# AWG_SFPs.net
KiCad netlist of a schematic drawn in Altium Designer
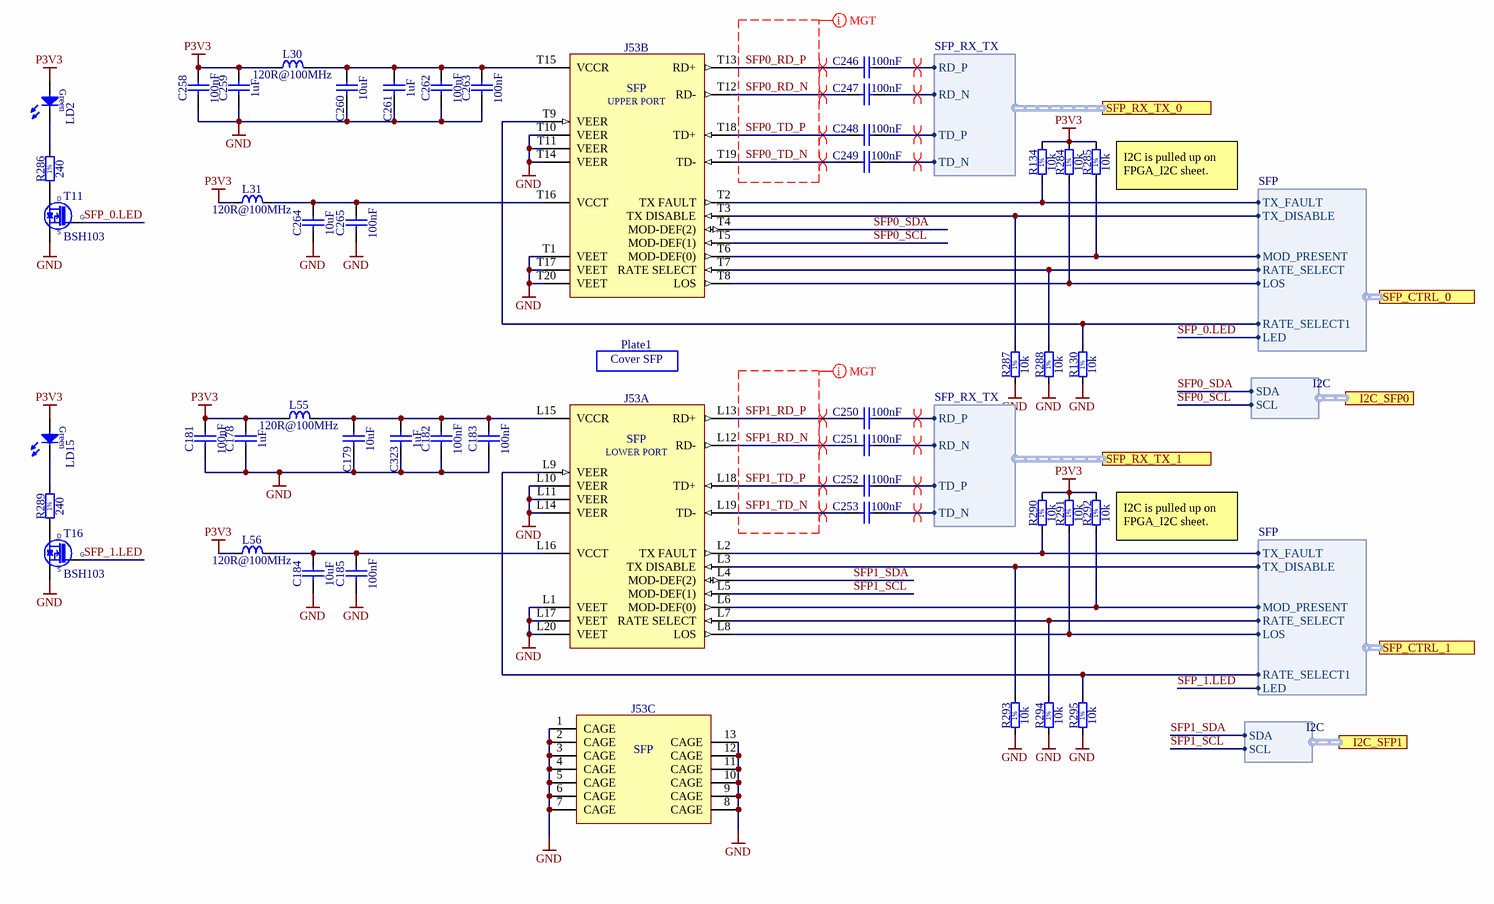
[diagram p0: AWG_SFPs.SchDoc]

(export (version "E")
  (design (tool "Eeschema 10.0.6"))
  (components
    (comp (ref "C178")
      (value "1uF")
      (footprint "CAPC1005X55N")
      (description "Non-polarised capacitor")
      (fields
        (field (name "PART NUMBER") "CC0402_1UF_16V_10%_X5R")
        (field (name "VOLTAGE") "16V")
        (field (name "AUTHOR") "CERN DEM JLC")
      )
      (libsource (lib "Capacitors") (part "Capacitor - non polarized"))
    )
    (comp (ref "C179")
      (value "10uF")
      (footprint "CAPC2012X95N")
      (description "Non-polarised capacitor")
      (fields
        (field (name "PART NUMBER") "CC0805_10UF_25V_10%_X5R")
        (field (name "VOLTAGE") "25V")
        (field (name "AUTHOR") "CERN DEM JLC")
      )
      (libsource (lib "Capacitors") (part "Capacitor - non polarized"))
    )
    (comp (ref "C181")
      (value "100nF")
      (footprint "CAPC1005X55N")
      (description "Non-polarised capacitor")
      (fields
        (field (name "PART NUMBER") "CC0402_100NF_16V_10%_X7R")
        (field (name "VOLTAGE") "16V")
        (field (name "AUTHOR") "CERN DEM JLC")
      )
      (libsource (lib "Capacitors") (part "Capacitor - non polarized"))
    )
    (comp (ref "C182")
      (value "100nF")
      (footprint "CAPC1005X55N")
      (description "Non-polarised capacitor")
      (fields
        (field (name "PART NUMBER") "CC0402_100NF_16V_10%_X7R")
        (field (name "VOLTAGE") "16V")
        (field (name "AUTHOR") "CERN DEM JLC")
      )
      (libsource (lib "Capacitors") (part "Capacitor - non polarized"))
    )
    (comp (ref "C183")
      (value "100nF")
      (footprint "CAPC1005X55N")
      (description "Non-polarised capacitor")
      (fields
        (field (name "PART NUMBER") "CC0402_100NF_16V_10%_X7R")
        (field (name "VOLTAGE") "16V")
        (field (name "AUTHOR") "CERN DEM JLC")
      )
      (libsource (lib "Capacitors") (part "Capacitor - non polarized"))
    )
    (comp (ref "C184")
      (value "10uF")
      (footprint "CAPC2012X95N")
      (description "Non-polarised capacitor")
      (fields
        (field (name "PART NUMBER") "CC0805_10UF_25V_10%_X5R")
        (field (name "VOLTAGE") "25V")
        (field (name "AUTHOR") "CERN DEM JLC")
      )
      (libsource (lib "Capacitors") (part "Capacitor - non polarized"))
    )
    (comp (ref "C185")
      (value "100nF")
      (footprint "CAPC1005X55N")
      (description "Non-polarised capacitor")
      (fields
        (field (name "PART NUMBER") "CC0402_100NF_16V_10%_X7R")
        (field (name "VOLTAGE") "16V")
        (field (name "AUTHOR") "CERN DEM JLC")
      )
      (libsource (lib "Capacitors") (part "Capacitor - non polarized"))
    )
    (comp (ref "C246")
      (value "100nF")
      (footprint "CAPC0603X33N")
      (description "Non-polarised capacitor")
      (fields
        (field (name "PART NUMBER") "CC0201_100NF_6.3V_10%_X5R")
        (field (name "VOLTAGE") "6.3V")
        (field (name "AUTHOR") "CERN DEM JLC")
      )
      (libsource (lib "Capacitors") (part "Capacitor - non polarized"))
    )
    (comp (ref "C247")
      (value "100nF")
      (footprint "CAPC0603X33N")
      (description "Non-polarised capacitor")
      (fields
        (field (name "PART NUMBER") "CC0201_100NF_6.3V_10%_X5R")
        (field (name "VOLTAGE") "6.3V")
        (field (name "AUTHOR") "CERN DEM JLC")
      )
      (libsource (lib "Capacitors") (part "Capacitor - non polarized"))
    )
    (comp (ref "C248")
      (value "100nF")
      (footprint "CAPC0603X33N")
      (description "Non-polarised capacitor")
      (fields
        (field (name "PART NUMBER") "CC0201_100NF_6.3V_10%_X5R")
        (field (name "VOLTAGE") "6.3V")
        (field (name "AUTHOR") "CERN DEM JLC")
      )
      (libsource (lib "Capacitors") (part "Capacitor - non polarized"))
    )
    (comp (ref "C249")
      (value "100nF")
      (footprint "CAPC0603X33N")
      (description "Non-polarised capacitor")
      (fields
        (field (name "PART NUMBER") "CC0201_100NF_6.3V_10%_X5R")
        (field (name "VOLTAGE") "6.3V")
        (field (name "AUTHOR") "CERN DEM JLC")
      )
      (libsource (lib "Capacitors") (part "Capacitor - non polarized"))
    )
    (comp (ref "C250")
      (value "100nF")
      (footprint "CAPC0603X33N")
      (description "Non-polarised capacitor")
      (fields
        (field (name "PART NUMBER") "CC0201_100NF_6.3V_10%_X5R")
        (field (name "VOLTAGE") "6.3V")
        (field (name "AUTHOR") "CERN DEM JLC")
      )
      (libsource (lib "Capacitors") (part "Capacitor - non polarized"))
    )
    (comp (ref "C251")
      (value "100nF")
      (footprint "CAPC0603X33N")
      (description "Non-polarised capacitor")
      (fields
        (field (name "PART NUMBER") "CC0201_100NF_6.3V_10%_X5R")
        (field (name "VOLTAGE") "6.3V")
        (field (name "AUTHOR") "CERN DEM JLC")
      )
      (libsource (lib "Capacitors") (part "Capacitor - non polarized"))
    )
    (comp (ref "C252")
      (value "100nF")
      (footprint "CAPC0603X33N")
      (description "Non-polarised capacitor")
      (fields
        (field (name "PART NUMBER") "CC0201_100NF_6.3V_10%_X5R")
        (field (name "VOLTAGE") "6.3V")
        (field (name "AUTHOR") "CERN DEM JLC")
      )
      (libsource (lib "Capacitors") (part "Capacitor - non polarized"))
    )
    (comp (ref "C253")
      (value "100nF")
      (footprint "CAPC0603X33N")
      (description "Non-polarised capacitor")
      (fields
        (field (name "PART NUMBER") "CC0201_100NF_6.3V_10%_X5R")
        (field (name "VOLTAGE") "6.3V")
        (field (name "AUTHOR") "CERN DEM JLC")
      )
      (libsource (lib "Capacitors") (part "Capacitor - non polarized"))
    )
    (comp (ref "C258")
      (value "100nF")
      (footprint "CAPC1005X55N")
      (description "Non-polarised capacitor")
      (fields
        (field (name "PART NUMBER") "CC0402_100NF_16V_10%_X7R")
        (field (name "VOLTAGE") "16V")
        (field (name "AUTHOR") "CERN DEM JLC")
      )
      (libsource (lib "Capacitors") (part "Capacitor - non polarized"))
    )
    (comp (ref "C259")
      (value "1uF")
      (footprint "CAPC1005X55N")
      (description "Non-polarised capacitor")
      (fields
        (field (name "PART NUMBER") "CC0402_1UF_16V_10%_X5R")
        (field (name "VOLTAGE") "16V")
        (field (name "AUTHOR") "CERN DEM JLC")
      )
      (libsource (lib "Capacitors") (part "Capacitor - non polarized"))
    )
    (comp (ref "C260")
      (value "10uF")
      (footprint "CAPC2012X95N")
      (description "Non-polarised capacitor")
      (fields
        (field (name "PART NUMBER") "CC0805_10UF_25V_10%_X5R")
        (field (name "VOLTAGE") "25V")
        (field (name "AUTHOR") "CERN DEM JLC")
      )
      (libsource (lib "Capacitors") (part "Capacitor - non polarized"))
    )
    (comp (ref "C261")
      (value "1uF")
      (footprint "CAPC1005X55N")
      (description "Non-polarised capacitor")
      (fields
        (field (name "PART NUMBER") "CC0402_1UF_16V_10%_X5R")
        (field (name "VOLTAGE") "16V")
        (field (name "AUTHOR") "CERN DEM JLC")
      )
      (libsource (lib "Capacitors") (part "Capacitor - non polarized"))
    )
    (comp (ref "C262")
      (value "100nF")
      (footprint "CAPC1005X55N")
      (description "Non-polarised capacitor")
      (fields
        (field (name "PART NUMBER") "CC0402_100NF_16V_10%_X7R")
        (field (name "VOLTAGE") "16V")
        (field (name "AUTHOR") "CERN DEM JLC")
      )
      (libsource (lib "Capacitors") (part "Capacitor - non polarized"))
    )
    (comp (ref "C263")
      (value "100nF")
      (footprint "CAPC1005X55N")
      (description "Non-polarised capacitor")
      (fields
        (field (name "PART NUMBER") "CC0402_100NF_16V_10%_X7R")
        (field (name "VOLTAGE") "16V")
        (field (name "AUTHOR") "CERN DEM JLC")
      )
      (libsource (lib "Capacitors") (part "Capacitor - non polarized"))
    )
    (comp (ref "C264")
      (value "10uF")
      (footprint "CAPC2012X95N")
      (description "Non-polarised capacitor")
      (fields
        (field (name "PART NUMBER") "CC0805_10UF_25V_10%_X5R")
        (field (name "VOLTAGE") "25V")
        (field (name "AUTHOR") "CERN DEM JLC")
      )
      (libsource (lib "Capacitors") (part "Capacitor - non polarized"))
    )
    (comp (ref "C265")
      (value "100nF")
      (footprint "CAPC1005X55N")
      (description "Non-polarised capacitor")
      (fields
        (field (name "PART NUMBER") "CC0402_100NF_16V_10%_X7R")
        (field (name "VOLTAGE") "16V")
        (field (name "AUTHOR") "CERN DEM JLC")
      )
      (libsource (lib "Capacitors") (part "Capacitor - non polarized"))
    )
    (comp (ref "C323")
      (value "1uF")
      (footprint "CAPC1005X55N")
      (description "Non-polarised capacitor")
      (fields
        (field (name "PART NUMBER") "CC0402_1UF_16V_10%_X5R")
        (field (name "VOLTAGE") "16V")
        (field (name "AUTHOR") "CERN DEM JLC")
      )
      (libsource (lib "Capacitors") (part "Capacitor - non polarized"))
    )
    (comp (ref "J53")
      (value "SFP")
      (footprint "MOLEX_75640-5001")
      (fields
        (field (name "PART NUMBER") "MOLEX_75640-5001")
        (field (name "MANUFACTURER") "MOLEX")
        (field (name "MANUFACTURER PART NUMBER") "75640-5001")
        (field (name "AUTHOR") "CERN DEM JLC")
      )
      (libsource (lib "Connectors") (part "MOLEX_75640-5001"))
    )
    (comp (ref "L30")
      (value "120R@100MHz")
      (footprint "INDC1608X65N")
      (description "Inductor")
      (fields
        (field (name "PART NUMBER") "IND0603_MURATA_BLM18SG121TN1D")
        (field (name "POWER") "3A")
        (field (name "AUTHOR") "CERN DEM JLC")
      )
      (libsource (lib "Inductors & Transformers") (part "Inductor"))
    )
    (comp (ref "L31")
      (value "120R@100MHz")
      (footprint "INDC1608X65N")
      (description "Inductor")
      (fields
        (field (name "PART NUMBER") "IND0603_MURATA_BLM18SG121TN1D")
        (field (name "POWER") "3A")
        (field (name "AUTHOR") "CERN DEM JLC")
      )
      (libsource (lib "Inductors & Transformers") (part "Inductor"))
    )
    (comp (ref "L55")
      (value "120R@100MHz")
      (footprint "INDC1608X65N")
      (description "Inductor")
      (fields
        (field (name "PART NUMBER") "IND0603_MURATA_BLM18SG121TN1D")
        (field (name "POWER") "3A")
        (field (name "AUTHOR") "CERN DEM JLC")
      )
      (libsource (lib "Inductors & Transformers") (part "Inductor"))
    )
    (comp (ref "L56")
      (value "120R@100MHz")
      (footprint "INDC1608X65N")
      (description "Inductor")
      (fields
        (field (name "PART NUMBER") "IND0603_MURATA_BLM18SG121TN1D")
        (field (name "POWER") "3A")
        (field (name "AUTHOR") "CERN DEM JLC")
      )
      (libsource (lib "Inductors & Transformers") (part "Inductor"))
    )
    (comp (ref "LD2")
      (value "Green")
      (footprint "LED_AVAGO_HSME-C120")
      (description "LED Green 1C 2A")
      (fields
        (field (name "PART NUMBER") "LED_AVAGO_HSME-C120")
        (field (name "MANUFACTURER") "AVAGO TECHNOLOGIES")
        (field (name "AUTHOR") "CERN DEM JMW")
      )
      (libsource (lib "ICs And Semiconductors") (part "LED Green 1C 2A"))
    )
    (comp (ref "LD15")
      (value "Green")
      (footprint "LED_AVAGO_HSME-C120")
      (description "LED Green 1C 2A")
      (fields
        (field (name "PART NUMBER") "LED_AVAGO_HSME-C120")
        (field (name "MANUFACTURER") "AVAGO TECHNOLOGIES")
        (field (name "AUTHOR") "CERN DEM JMW")
      )
      (libsource (lib "ICs And Semiconductors") (part "LED Green 1C 2A"))
    )
    (comp (ref "Plate1")
      (value "Cover SFP")
      (footprint "AMPHENOL_U77A11108000P")
      (description "Plastic Dust Cover SFP Cage")
      (fields
        (field (name "PART NUMBER") "AMPHENOL_U77A11108000P")
        (field (name "MANUFACTURER") "AMPHENOL")
        (field (name "AUTHOR") "CERN DEM BC")
      )
      (libsource (lib "Eletro-mechanical") (part "SFP Cover No Pin"))
    )
    (comp (ref "R130")
      (value "10k")
      (footprint "RESC1005X40N")
      (description "Resistor - 1%")
      (fields
        (field (name "PART NUMBER") "R0402_10K_1%_0.0625W_100PPM")
        (field (name "POWER") "0.0625W")
        (field (name "AUTHOR") "CERN DEM JLC")
      )
      (libsource (lib "Resistors") (part "Resistor - 1%"))
    )
    (comp (ref "R134")
      (value "10k")
      (footprint "RESC1005X40N")
      (description "Resistor - 1%")
      (fields
        (field (name "PART NUMBER") "R0402_10K_1%_0.0625W_100PPM")
        (field (name "POWER") "0.0625W")
        (field (name "AUTHOR") "CERN DEM JLC")
      )
      (libsource (lib "Resistors") (part "Resistor - 1%"))
    )
    (comp (ref "R284")
      (value "10k")
      (footprint "RESC1005X40N")
      (description "Resistor - 1%")
      (fields
        (field (name "PART NUMBER") "R0402_10K_1%_0.0625W_100PPM")
        (field (name "POWER") "0.0625W")
        (field (name "AUTHOR") "CERN DEM JLC")
      )
      (libsource (lib "Resistors") (part "Resistor - 1%"))
    )
    (comp (ref "R285")
      (value "10k")
      (footprint "RESC1005X40N")
      (description "Resistor - 1%")
      (fields
        (field (name "PART NUMBER") "R0402_10K_1%_0.0625W_100PPM")
        (field (name "POWER") "0.0625W")
        (field (name "AUTHOR") "CERN DEM JLC")
      )
      (libsource (lib "Resistors") (part "Resistor - 1%"))
    )
    (comp (ref "R286")
      (value "240")
      (footprint "RESC1005X40N")
      (description "Resistor - 1%")
      (fields
        (field (name "PART NUMBER") "R0402_240R_1%_0.0625W_100PPM")
        (field (name "POWER") "0.0625W")
        (field (name "AUTHOR") "CERN DEM JLC")
      )
      (libsource (lib "Resistors") (part "Resistor - 1%"))
    )
    (comp (ref "R287")
      (value "10k")
      (footprint "RESC1005X40N")
      (description "Resistor - 1%")
      (fields
        (field (name "PART NUMBER") "R0402_10K_1%_0.0625W_100PPM")
        (field (name "POWER") "0.0625W")
        (field (name "AUTHOR") "CERN DEM JLC")
      )
      (libsource (lib "Resistors") (part "Resistor - 1%"))
    )
    (comp (ref "R288")
      (value "10k")
      (footprint "RESC1005X40N")
      (description "Resistor - 1%")
      (fields
        (field (name "PART NUMBER") "R0402_10K_1%_0.0625W_100PPM")
        (field (name "POWER") "0.0625W")
        (field (name "AUTHOR") "CERN DEM JLC")
      )
      (libsource (lib "Resistors") (part "Resistor - 1%"))
    )
    (comp (ref "R289")
      (value "240")
      (footprint "RESC1005X40N")
      (description "Resistor - 1%")
      (fields
        (field (name "PART NUMBER") "R0402_240R_1%_0.0625W_100PPM")
        (field (name "POWER") "0.0625W")
        (field (name "AUTHOR") "CERN DEM JLC")
      )
      (libsource (lib "Resistors") (part "Resistor - 1%"))
    )
    (comp (ref "R290")
      (value "10k")
      (footprint "RESC1005X40N")
      (description "Resistor - 1%")
      (fields
        (field (name "PART NUMBER") "R0402_10K_1%_0.0625W_100PPM")
        (field (name "POWER") "0.0625W")
        (field (name "AUTHOR") "CERN DEM JLC")
      )
      (libsource (lib "Resistors") (part "Resistor - 1%"))
    )
    (comp (ref "R291")
      (value "10k")
      (footprint "RESC1005X40N")
      (description "Resistor - 1%")
      (fields
        (field (name "PART NUMBER") "R0402_10K_1%_0.0625W_100PPM")
        (field (name "POWER") "0.0625W")
        (field (name "AUTHOR") "CERN DEM JLC")
      )
      (libsource (lib "Resistors") (part "Resistor - 1%"))
    )
    (comp (ref "R292")
      (value "10k")
      (footprint "RESC1005X40N")
      (description "Resistor - 1%")
      (fields
        (field (name "PART NUMBER") "R0402_10K_1%_0.0625W_100PPM")
        (field (name "POWER") "0.0625W")
        (field (name "AUTHOR") "CERN DEM JLC")
      )
      (libsource (lib "Resistors") (part "Resistor - 1%"))
    )
    (comp (ref "R293")
      (value "10k")
      (footprint "RESC1005X40N")
      (description "Resistor - 1%")
      (fields
        (field (name "PART NUMBER") "R0402_10K_1%_0.0625W_100PPM")
        (field (name "POWER") "0.0625W")
        (field (name "AUTHOR") "CERN DEM JLC")
      )
      (libsource (lib "Resistors") (part "Resistor - 1%"))
    )
    (comp (ref "R294")
      (value "10k")
      (footprint "RESC1005X40N")
      (description "Resistor - 1%")
      (fields
        (field (name "PART NUMBER") "R0402_10K_1%_0.0625W_100PPM")
        (field (name "POWER") "0.0625W")
        (field (name "AUTHOR") "CERN DEM JLC")
      )
      (libsource (lib "Resistors") (part "Resistor - 1%"))
    )
    (comp (ref "R295")
      (value "10k")
      (footprint "RESC1005X40N")
      (description "Resistor - 1%")
      (fields
        (field (name "PART NUMBER") "R0402_10K_1%_0.0625W_100PPM")
        (field (name "POWER") "0.0625W")
        (field (name "AUTHOR") "CERN DEM JLC")
      )
      (libsource (lib "Resistors") (part "Resistor - 1%"))
    )
    (comp (ref "T11")
      (value "BSH103")
      (footprint "SOT95P230X110-3N")
      (description "N-CHANNEL MOSFET WITH DIODE")
      (fields (field (name "MANUFACTURER") "NEXPERIA") (field (name "AUTHOR") "CERN DEM JLC"))
      (libsource (lib "ICs And Semiconductors") (part "N-MOSFET-D 1G 2S 3D"))
    )
    (comp (ref "T16")
      (value "BSH103")
      (footprint "SOT95P230X110-3N")
      (description "N-CHANNEL MOSFET WITH DIODE")
      (fields (field (name "MANUFACTURER") "NEXPERIA") (field (name "AUTHOR") "CERN DEM JLC"))
      (libsource (lib "ICs And Semiconductors") (part "N-MOSFET-D 1G 2S 3D"))
    )
  )
  (nets
    (net (code "4") (name "/SFP0_RD_N") (class "Default")
      (node (ref "C247") (pin "1") (pinfunction "1_1") (pintype "passive"))
      (node (ref "J53") (pin "T12") (pinfunction "RD-_T12") (pintype "output"))
    )
    (net (code "5") (name "/SFP0_RD_P") (class "Default")
      (node (ref "C246") (pin "1") (pinfunction "1_1") (pintype "passive"))
      (node (ref "J53") (pin "T13") (pinfunction "RD+_T13") (pintype "output"))
    )
    (net (code "6") (name "/SFP0_SCL") (class "Default")
      (node (ref "J53") (pin "T5") (pinfunction "MOD-DEF(1)_T5") (pintype "input"))
    )
    (net (code "7") (name "/SFP0_SDA") (class "Default")
      (node (ref "J53") (pin "T4") (pinfunction "MOD-DEF(2)_T4") (pintype "bidirectional"))
    )
    (net (code "8") (name "/SFP0_TD_N") (class "Default")
      (node (ref "C249") (pin "1") (pinfunction "1_1") (pintype "passive"))
      (node (ref "J53") (pin "T19") (pinfunction "TD-_T19") (pintype "input"))
    )
    (net (code "9") (name "/SFP0_TD_P") (class "Default")
      (node (ref "C248") (pin "1") (pinfunction "1_1") (pintype "passive"))
      (node (ref "J53") (pin "T18") (pinfunction "TD+_T18") (pintype "input"))
    )
    (net (code "10") (name "/SFP1_RD_N") (class "Default")
      (node (ref "C251") (pin "1") (pinfunction "1_1") (pintype "passive"))
      (node (ref "J53") (pin "L12") (pinfunction "RD-_L12") (pintype "output"))
    )
    (net (code "11") (name "/SFP1_RD_P") (class "Default")
      (node (ref "C250") (pin "1") (pinfunction "1_1") (pintype "passive"))
      (node (ref "J53") (pin "L13") (pinfunction "RD+_L13") (pintype "output"))
    )
    (net (code "12") (name "/SFP1_SCL") (class "Default")
      (node (ref "J53") (pin "L5") (pinfunction "MOD-DEF(1)_L5") (pintype "input"))
    )
    (net (code "13") (name "/SFP1_SDA") (class "Default")
      (node (ref "J53") (pin "L4") (pinfunction "MOD-DEF(2)_L4") (pintype "bidirectional"))
    )
    (net (code "14") (name "/SFP1_TD_N") (class "Default")
      (node (ref "C253") (pin "1") (pinfunction "1_1") (pintype "passive"))
      (node (ref "J53") (pin "L19") (pinfunction "TD-_L19") (pintype "input"))
    )
    (net (code "15") (name "/SFP1_TD_P") (class "Default")
      (node (ref "C252") (pin "1") (pinfunction "1_1") (pintype "passive"))
      (node (ref "J53") (pin "L18") (pinfunction "TD+_L18") (pintype "input"))
    )
    (net (code "16") (name "/SFP_0.LED") (class "Default")
      (node (ref "T11") (pin "1") (pinfunction "G_1") (pintype "passive"))
    )
    (net (code "17") (name "/SFP_1.LED") (class "Default")
      (node (ref "T16") (pin "1") (pinfunction "G_1") (pintype "passive"))
    )
    (net (code "21") (name "GND") (class "Default")
      (node (ref "C178") (pin "1") (pinfunction "1_1") (pintype "passive"))
      (node (ref "C179") (pin "1") (pinfunction "1_1") (pintype "passive"))
      (node (ref "C181") (pin "1") (pinfunction "1_1") (pintype "passive"))
      (node (ref "C182") (pin "1") (pinfunction "1_1") (pintype "passive"))
      (node (ref "C183") (pin "1") (pinfunction "1_1") (pintype "passive"))
      (node (ref "C184") (pin "1") (pinfunction "1_1") (pintype "passive"))
      (node (ref "C185") (pin "1") (pinfunction "1_1") (pintype "passive"))
      (node (ref "C258") (pin "1") (pinfunction "1_1") (pintype "passive"))
      (node (ref "C259") (pin "1") (pinfunction "1_1") (pintype "passive"))
      (node (ref "C260") (pin "1") (pinfunction "1_1") (pintype "passive"))
      (node (ref "C261") (pin "1") (pinfunction "1_1") (pintype "passive"))
      (node (ref "C262") (pin "1") (pinfunction "1_1") (pintype "passive"))
      (node (ref "C263") (pin "1") (pinfunction "1_1") (pintype "passive"))
      (node (ref "C264") (pin "1") (pinfunction "1_1") (pintype "passive"))
      (node (ref "C265") (pin "1") (pinfunction "1_1") (pintype "passive"))
      (node (ref "C323") (pin "1") (pinfunction "1_1") (pintype "passive"))
      (node (ref "J53") (pin "1") (pinfunction "CAGE_1") (pintype "power_in"))
      (node (ref "J53") (pin "10") (pinfunction "CAGE_10") (pintype "power_in"))
      (node (ref "J53") (pin "11") (pinfunction "CAGE_11") (pintype "power_in"))
      (node (ref "J53") (pin "12") (pinfunction "CAGE_12") (pintype "power_in"))
      (node (ref "J53") (pin "13") (pinfunction "CAGE_13") (pintype "power_in"))
      (node (ref "J53") (pin "2") (pinfunction "CAGE_2") (pintype "power_in"))
      (node (ref "J53") (pin "3") (pinfunction "CAGE_3") (pintype "power_in"))
      (node (ref "J53") (pin "4") (pinfunction "CAGE_4") (pintype "power_in"))
      (node (ref "J53") (pin "5") (pinfunction "CAGE_5") (pintype "power_in"))
      (node (ref "J53") (pin "6") (pinfunction "CAGE_6") (pintype "power_in"))
      (node (ref "J53") (pin "7") (pinfunction "CAGE_7") (pintype "power_in"))
      (node (ref "J53") (pin "8") (pinfunction "CAGE_8") (pintype "power_in"))
      (node (ref "J53") (pin "9") (pinfunction "CAGE_9") (pintype "power_in"))
      (node (ref "J53") (pin "L1") (pinfunction "VEET_L1") (pintype "power_in"))
      (node (ref "J53") (pin "L10") (pinfunction "VEER_L10") (pintype "power_in"))
      (node (ref "J53") (pin "L11") (pinfunction "VEER_L11") (pintype "power_in"))
      (node (ref "J53") (pin "L14") (pinfunction "VEER_L14") (pintype "power_in"))
      (node (ref "J53") (pin "L17") (pinfunction "VEET_L17") (pintype "power_in"))
      (node (ref "J53") (pin "L20") (pinfunction "VEET_L20") (pintype "power_in"))
      (node (ref "J53") (pin "T1") (pinfunction "VEET_T1") (pintype "power_in"))
      (node (ref "J53") (pin "T10") (pinfunction "VEER_T10") (pintype "power_in"))
      (node (ref "J53") (pin "T11") (pinfunction "VEER_T11") (pintype "power_in"))
      (node (ref "J53") (pin "T14") (pinfunction "VEER_T14") (pintype "power_in"))
      (node (ref "J53") (pin "T17") (pinfunction "VEET_T17") (pintype "power_in"))
      (node (ref "J53") (pin "T20") (pinfunction "VEET_T20") (pintype "power_in"))
      (node (ref "R130") (pin "1") (pinfunction "1_1") (pintype "passive"))
      (node (ref "R287") (pin "1") (pinfunction "1_1") (pintype "passive"))
      (node (ref "R288") (pin "1") (pinfunction "1_1") (pintype "passive"))
      (node (ref "R293") (pin "1") (pinfunction "1_1") (pintype "passive"))
      (node (ref "R294") (pin "1") (pinfunction "1_1") (pintype "passive"))
      (node (ref "R295") (pin "1") (pinfunction "1_1") (pintype "passive"))
      (node (ref "T11") (pin "2") (pinfunction "S_2") (pintype "passive"))
      (node (ref "T16") (pin "2") (pinfunction "S_2") (pintype "passive"))
    )
    (net (code "22") (name "Net-(J53A-LOS)") (class "Default")
      (node (ref "J53") (pin "L8") (pinfunction "LOS_L8") (pintype "output"))
      (node (ref "R291") (pin "1") (pinfunction "1_1") (pintype "passive"))
    )
    (net (code "23") (name "Net-(J53A-MOD-DEF(0))") (class "Default")
      (node (ref "J53") (pin "L6") (pinfunction "MOD-DEF(0)_L6") (pintype "output"))
      (node (ref "R292") (pin "1") (pinfunction "1_1") (pintype "passive"))
    )
    (net (code "24") (name "Net-(J53A-RATE_SELECT)") (class "Default")
      (node (ref "J53") (pin "L7") (pinfunction "RATE_SELECT_L7") (pintype "input"))
      (node (ref "R294") (pin "2") (pinfunction "2_2") (pintype "passive"))
    )
    (net (code "25") (name "Net-(J53A-TX_DISABLE)") (class "Default")
      (node (ref "J53") (pin "L3") (pinfunction "TX_DISABLE_L3") (pintype "input"))
      (node (ref "R293") (pin "2") (pinfunction "2_2") (pintype "passive"))
    )
    (net (code "26") (name "Net-(J53A-TX_FAULT)") (class "Default")
      (node (ref "J53") (pin "L2") (pinfunction "TX_FAULT_L2") (pintype "output"))
      (node (ref "R290") (pin "1") (pinfunction "1_1") (pintype "passive"))
    )
    (net (code "27") (name "Net-(J53A-VCCR)") (class "Default")
      (node (ref "C179") (pin "2") (pinfunction "2_2") (pintype "passive"))
      (node (ref "C182") (pin "2") (pinfunction "2_2") (pintype "passive"))
      (node (ref "C183") (pin "2") (pinfunction "2_2") (pintype "passive"))
      (node (ref "C323") (pin "2") (pinfunction "2_2") (pintype "passive"))
      (node (ref "J53") (pin "L15") (pinfunction "VCCR_L15") (pintype "power_in"))
      (node (ref "L55") (pin "2") (pinfunction "2_2") (pintype "passive"))
    )
    (net (code "28") (name "Net-(J53A-VCCT)") (class "Default")
      (node (ref "C184") (pin "2") (pinfunction "2_2") (pintype "passive"))
      (node (ref "C185") (pin "2") (pinfunction "2_2") (pintype "passive"))
      (node (ref "J53") (pin "L16") (pinfunction "VCCT_L16") (pintype "power_in"))
      (node (ref "L56") (pin "2") (pinfunction "2_2") (pintype "passive"))
    )
    (net (code "29") (name "Net-(J53A-VEER-PadL9)") (class "Default")
      (node (ref "J53") (pin "L9") (pinfunction "VEER_L9") (pintype "input"))
      (node (ref "R295") (pin "2") (pinfunction "2_2") (pintype "passive"))
    )
    (net (code "30") (name "Net-(J53B-LOS)") (class "Default")
      (node (ref "J53") (pin "T8") (pinfunction "LOS_T8") (pintype "output"))
      (node (ref "R284") (pin "1") (pinfunction "1_1") (pintype "passive"))
    )
    (net (code "31") (name "Net-(J53B-MOD-DEF(0))") (class "Default")
      (node (ref "J53") (pin "T6") (pinfunction "MOD-DEF(0)_T6") (pintype "output"))
      (node (ref "R285") (pin "1") (pinfunction "1_1") (pintype "passive"))
    )
    (net (code "32") (name "Net-(J53B-RATE_SELECT)") (class "Default")
      (node (ref "J53") (pin "T7") (pinfunction "RATE_SELECT_T7") (pintype "input"))
      (node (ref "R288") (pin "2") (pinfunction "2_2") (pintype "passive"))
    )
    (net (code "33") (name "Net-(J53B-TX_DISABLE)") (class "Default")
      (node (ref "J53") (pin "T3") (pinfunction "TX_DISABLE_T3") (pintype "input"))
      (node (ref "R287") (pin "2") (pinfunction "2_2") (pintype "passive"))
    )
    (net (code "34") (name "Net-(J53B-TX_FAULT)") (class "Default")
      (node (ref "J53") (pin "T2") (pinfunction "TX_FAULT_T2") (pintype "output"))
      (node (ref "R134") (pin "1") (pinfunction "1_1") (pintype "passive"))
    )
    (net (code "35") (name "Net-(J53B-VCCR)") (class "Default")
      (node (ref "C260") (pin "2") (pinfunction "2_2") (pintype "passive"))
      (node (ref "C261") (pin "2") (pinfunction "2_2") (pintype "passive"))
      (node (ref "C262") (pin "2") (pinfunction "2_2") (pintype "passive"))
      (node (ref "C263") (pin "2") (pinfunction "2_2") (pintype "passive"))
      (node (ref "J53") (pin "T15") (pinfunction "VCCR_T15") (pintype "power_in"))
      (node (ref "L30") (pin "2") (pinfunction "2_2") (pintype "passive"))
    )
    (net (code "36") (name "Net-(J53B-VCCT)") (class "Default")
      (node (ref "C264") (pin "2") (pinfunction "2_2") (pintype "passive"))
      (node (ref "C265") (pin "2") (pinfunction "2_2") (pintype "passive"))
      (node (ref "J53") (pin "T16") (pinfunction "VCCT_T16") (pintype "power_in"))
      (node (ref "L31") (pin "2") (pinfunction "2_2") (pintype "passive"))
    )
    (net (code "37") (name "Net-(J53B-VEER-PadT9)") (class "Default")
      (node (ref "J53") (pin "T9") (pinfunction "VEER_T9") (pintype "input"))
      (node (ref "R130") (pin "2") (pinfunction "2_2") (pintype "passive"))
    )
    (net (code "38") (name "Net-(LD2-C)") (class "Default")
      (node (ref "LD2") (pin "1") (pinfunction "C_1") (pintype "passive"))
      (node (ref "R286") (pin "2") (pinfunction "2_2") (pintype "passive"))
    )
    (net (code "39") (name "Net-(LD15-C)") (class "Default")
      (node (ref "LD15") (pin "1") (pinfunction "C_1") (pintype "passive"))
      (node (ref "R289") (pin "2") (pinfunction "2_2") (pintype "passive"))
    )
    (net (code "40") (name "Net-(T11-D)") (class "Default")
      (node (ref "R286") (pin "1") (pinfunction "1_1") (pintype "passive"))
      (node (ref "T11") (pin "3") (pinfunction "D_3") (pintype "passive"))
    )
    (net (code "41") (name "Net-(T16-D)") (class "Default")
      (node (ref "R289") (pin "1") (pinfunction "1_1") (pintype "passive"))
      (node (ref "T16") (pin "3") (pinfunction "D_3") (pintype "passive"))
    )
    (net (code "42") (name "P3V3") (class "Default")
      (node (ref "C178") (pin "2") (pinfunction "2_2") (pintype "passive"))
      (node (ref "C181") (pin "2") (pinfunction "2_2") (pintype "passive"))
      (node (ref "C258") (pin "2") (pinfunction "2_2") (pintype "passive"))
      (node (ref "C259") (pin "2") (pinfunction "2_2") (pintype "passive"))
      (node (ref "L30") (pin "1") (pinfunction "1_1") (pintype "passive"))
      (node (ref "L31") (pin "1") (pinfunction "1_1") (pintype "passive"))
      (node (ref "L55") (pin "1") (pinfunction "1_1") (pintype "passive"))
      (node (ref "L56") (pin "1") (pinfunction "1_1") (pintype "passive"))
      (node (ref "LD15") (pin "2") (pinfunction "A_2") (pintype "passive"))
      (node (ref "LD2") (pin "2") (pinfunction "A_2") (pintype "passive"))
      (node (ref "R134") (pin "2") (pinfunction "2_2") (pintype "passive"))
      (node (ref "R284") (pin "2") (pinfunction "2_2") (pintype "passive"))
      (node (ref "R285") (pin "2") (pinfunction "2_2") (pintype "passive"))
      (node (ref "R290") (pin "2") (pinfunction "2_2") (pintype "passive"))
      (node (ref "R291") (pin "2") (pinfunction "2_2") (pintype "passive"))
      (node (ref "R292") (pin "2") (pinfunction "2_2") (pintype "passive"))
    )
    (net (code "43") (name "unconnected-(C246-Pad2)") (class "Default")
      (node (ref "C246") (pin "2") (pinfunction "2_2") (pintype "passive"))
    )
    (net (code "44") (name "unconnected-(C247-Pad2)") (class "Default")
      (node (ref "C247") (pin "2") (pinfunction "2_2") (pintype "passive"))
    )
    (net (code "45") (name "unconnected-(C248-Pad2)") (class "Default")
      (node (ref "C248") (pin "2") (pinfunction "2_2") (pintype "passive"))
    )
    (net (code "46") (name "unconnected-(C249-Pad2)") (class "Default")
      (node (ref "C249") (pin "2") (pinfunction "2_2") (pintype "passive"))
    )
    (net (code "47") (name "unconnected-(C250-Pad2)") (class "Default")
      (node (ref "C250") (pin "2") (pinfunction "2_2") (pintype "passive"))
    )
    (net (code "48") (name "unconnected-(C251-Pad2)") (class "Default")
      (node (ref "C251") (pin "2") (pinfunction "2_2") (pintype "passive"))
    )
    (net (code "49") (name "unconnected-(C252-Pad2)") (class "Default")
      (node (ref "C252") (pin "2") (pinfunction "2_2") (pintype "passive"))
    )
    (net (code "50") (name "unconnected-(C253-Pad2)") (class "Default")
      (node (ref "C253") (pin "2") (pinfunction "2_2") (pintype "passive"))
    )
  )
)
